# 03_Mechanicals.net
KiCad netlist of a schematic drawn in Altium Designer
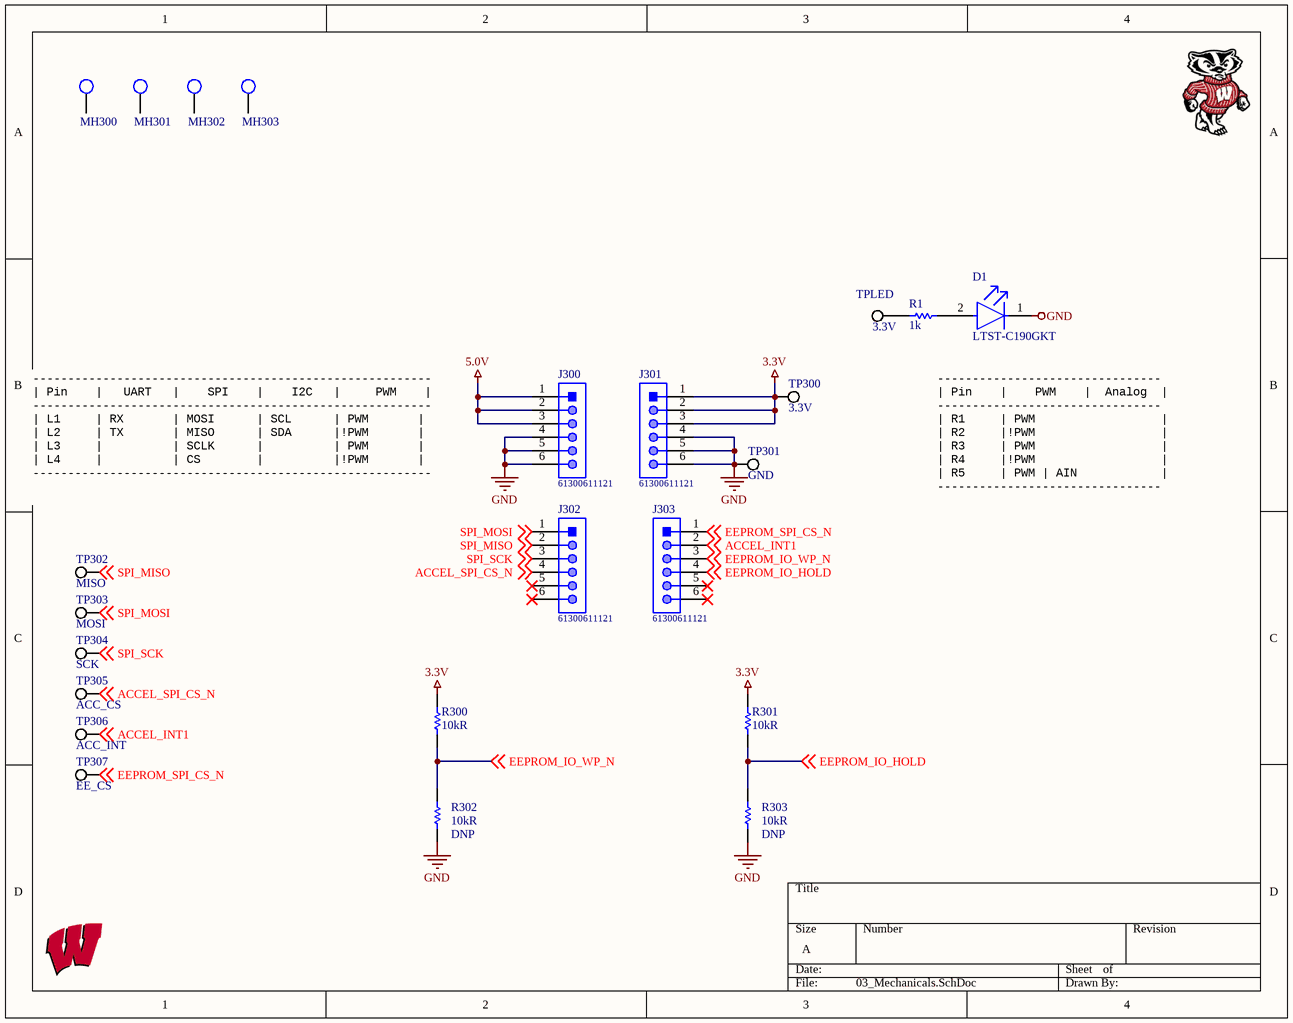
[diagram p0: 03_Mechanicals.SchDoc]

(export (version "E")
  (design (tool "Eeschema 10.0.6"))
  (components
    (comp (ref "D1")
      (value "LTST-C190GKT")
      (footprint "FP-LTST-C190GKT-MFG")
      (description "LED GREEN CLEAR CHIP SMD")
      (fields (field (name "VOLTAGE") "2V"))
      (libsource (lib "Altium Content Vault") (part "8706943c75ba83719d021d2fdc84c58"))
    )
    (comp (ref "J300")
      (value "61300611121")
      (footprint "61300611121")
      (description "THT Vertical Pin Header WR-PHD, Pitch 2.54 mm, Single Row, 6 pins")
      (fields (field (name "MANUFACTURER") "Wurth Elektronik") (field (name "PUBLISHER") "WurthElektronik"))
      (libsource (lib "") (part "WE-CN-1P-M-R6_1"))
    )
    (comp (ref "J301")
      (value "61300611121")
      (footprint "61300611121")
      (description "THT Vertical Pin Header WR-PHD, Pitch 2.54 mm, Single Row, 6 pins")
      (fields (field (name "MANUFACTURER") "Wurth Elektronik") (field (name "PUBLISHER") "WurthElektronik"))
      (libsource (lib "Altium Content Vault") (part "WE-CN-1P-M-R6"))
    )
    (comp (ref "J302")
      (value "61300611121")
      (footprint "61300611121")
      (description "THT Vertical Pin Header WR-PHD, Pitch 2.54 mm, Single Row, 6 pins")
      (fields (field (name "MANUFACTURER") "Wurth Elektronik") (field (name "PUBLISHER") "WurthElektronik"))
      (libsource (lib "") (part "WE-CN-1P-M-R6_1"))
    )
    (comp (ref "J303")
      (value "61300611121")
      (footprint "61300611121")
      (description "THT Vertical Pin Header WR-PHD, Pitch 2.54 mm, Single Row, 6 pins")
      (fields (field (name "MANUFACTURER") "Wurth Elektronik") (field (name "PUBLISHER") "WurthElektronik"))
      (libsource (lib "Altium Content Vault") (part "WE-CN-1P-M-R6"))
    )
    (comp (ref "MH300")
      (value "MHOLE_2_55MM")
      (footprint "MHOLE_2_55MM")
      (description "Mounting Holde")
      (fields (field (name "MANUFACTURER PART NUMBER") "UW MTHOLE"))
      (libsource (lib "ece315-2018-fall") (part "MHOLE_2_55MM"))
    )
    (comp (ref "MH301")
      (value "MHOLE_2_55MM")
      (footprint "MHOLE_2_55MM")
      (description "Mounting Holde")
      (fields (field (name "MANUFACTURER PART NUMBER") "UW MTHOLE"))
      (libsource (lib "ece315-2018-fall") (part "MHOLE_2_55MM"))
    )
    (comp (ref "MH302")
      (value "MHOLE_2_55MM")
      (footprint "MHOLE_2_55MM")
      (description "Mounting Holde")
      (fields (field (name "MANUFACTURER PART NUMBER") "UW MTHOLE"))
      (libsource (lib "ece315-2018-fall") (part "MHOLE_2_55MM"))
    )
    (comp (ref "MH303")
      (value "MHOLE_2_55MM")
      (footprint "MHOLE_2_55MM")
      (description "Mounting Holde")
      (fields (field (name "MANUFACTURER PART NUMBER") "UW MTHOLE"))
      (libsource (lib "ece315-2018-fall") (part "MHOLE_2_55MM"))
    )
    (comp (ref "R1")
      (value "1k")
      (footprint "RESC2013X60X35ML10T20")
      (description "Chip Resistor, 1 KOhm, +/- 1%, 125 mW, -55 to 155 degC, 0805 (2012 Metric), RoHS, Tape and Reel")
      (fields (field (name "TOLERANCE") "1%") (field (name "MANUFACTURER") "Yageo"))
      (libsource (lib "Altium Content Vault") (part "RES-2"))
    )
    (comp (ref "R300")
      (value "RC0805FR-0710KL")
      (footprint "RESC2013X60X35NL10T20")
      (description "Chip Resistor, 10 KOhm, +/- 1%, 0.125 W, -55 to 155 degC, 0805 (2012 Metric), RoHS, Tape and Reel")
      (fields
        (field (name "MANUFACTURER") "Yageo")
        (field (name "RESISTANCE") "10kR")
        (field (name "TOLERANCE") "1%")
      )
      (libsource (lib "Altium Content Vault") (part "RES-2"))
    )
    (comp (ref "R301")
      (value "RC0805FR-0710KL")
      (footprint "RESC2013X60X35NL10T20")
      (description "Chip Resistor, 10 KOhm, +/- 1%, 0.125 W, -55 to 155 degC, 0805 (2012 Metric), RoHS, Tape and Reel")
      (fields
        (field (name "MANUFACTURER") "Yageo")
        (field (name "RESISTANCE") "10kR")
        (field (name "TOLERANCE") "1%")
      )
      (libsource (lib "Altium Content Vault") (part "RES-2"))
    )
    (comp (ref "R302")
      (value "DNP")
      (footprint "RESC2013X60X35NL10T20")
      (description "Chip Resistor, 10 KOhm, +/- 1%, 0.125 W, -55 to 155 degC, 0805 (2012 Metric), RoHS, Tape and Reel")
      (fields
        (field (name "MANUFACTURER") "Yageo")
        (field (name "RESISTANCE") "10kR")
        (field (name "TOLERANCE") "1%")
      )
      (libsource (lib "Altium Content Vault") (part "RES-2"))
    )
    (comp (ref "R303")
      (value "DNP")
      (footprint "RESC2013X60X35NL10T20")
      (description "Chip Resistor, 10 KOhm, +/- 1%, 0.125 W, -55 to 155 degC, 0805 (2012 Metric), RoHS, Tape and Reel")
      (fields
        (field (name "MANUFACTURER") "Yageo")
        (field (name "RESISTANCE") "10kR")
        (field (name "TOLERANCE") "1%")
      )
      (libsource (lib "Altium Content Vault") (part "RES-2"))
    )
    (comp (ref "TP300")
      (value "3.3V")
      (footprint "KSTN-5019_V")
      (description "Test Point, 1 Position SMD, RoHS, Tape and Reel")
      (libsource (lib "Altium Content Vault") (part "TESTPOINT_WHITE"))
    )
    (comp (ref "TP301")
      (value "GND")
      (footprint "KSTN-5019_V")
      (description "Test Point, 1 Position SMD, RoHS, Tape and Reel")
      (libsource (lib "Altium Content Vault") (part "TESTPOINT_WHITE"))
    )
    (comp (ref "TP302")
      (value "MISO")
      (footprint "KSTN-5019_V")
      (description "Test Point, 1 Position SMD, RoHS, Tape and Reel")
      (libsource (lib "Altium Content Vault") (part "TESTPOINT_WHITE"))
    )
    (comp (ref "TP303")
      (value "MOSI")
      (footprint "KSTN-5019_V")
      (description "Test Point, 1 Position SMD, RoHS, Tape and Reel")
      (libsource (lib "Altium Content Vault") (part "TESTPOINT_WHITE"))
    )
    (comp (ref "TP304")
      (value "SCK")
      (footprint "KSTN-5019_V")
      (description "Test Point, 1 Position SMD, RoHS, Tape and Reel")
      (libsource (lib "Altium Content Vault") (part "TESTPOINT_WHITE"))
    )
    (comp (ref "TP305")
      (value "ACC_CS")
      (footprint "KSTN-5019_V")
      (description "Test Point, 1 Position SMD, RoHS, Tape and Reel")
      (libsource (lib "Altium Content Vault") (part "TESTPOINT_WHITE"))
    )
    (comp (ref "TP306")
      (value "ACC_INT")
      (footprint "KSTN-5019_V")
      (description "Test Point, 1 Position SMD, RoHS, Tape and Reel")
      (libsource (lib "Altium Content Vault") (part "TESTPOINT_WHITE"))
    )
    (comp (ref "TP307")
      (value "EE_CS")
      (footprint "KSTN-5019_V")
      (description "Test Point, 1 Position SMD, RoHS, Tape and Reel")
      (libsource (lib "Altium Content Vault") (part "TESTPOINT_WHITE"))
    )
    (comp (ref "TPLED")
      (value "3.3V")
      (footprint "KSTN-5019_V")
      (description "Test Point, 1 Position SMD, RoHS, Tape and Reel")
      (libsource (lib "Altium Content Vault") (part "TESTPOINT_WHITE"))
    )
  )
  (nets
    (net (code "1") (name "3.3V") (class "Default")
      (node (ref "J301") (pin "1") (pinfunction "1_1") (pintype "passive"))
      (node (ref "J301") (pin "2") (pinfunction "2_2") (pintype "passive"))
      (node (ref "J301") (pin "3") (pinfunction "3_3") (pintype "passive"))
      (node (ref "R300") (pin "1") (pinfunction "1_1") (pintype "passive"))
      (node (ref "R301") (pin "1") (pinfunction "1_1") (pintype "passive"))
      (node (ref "TP300") (pin "1") (pinfunction "1_1") (pintype "passive"))
    )
    (net (code "2") (name "5.0V") (class "Default")
      (node (ref "J300") (pin "1") (pinfunction "1_1") (pintype "passive"))
      (node (ref "J300") (pin "2") (pinfunction "2_2") (pintype "passive"))
      (node (ref "J300") (pin "3") (pinfunction "3_3") (pintype "passive"))
    )
    (net (code "3") (name "ACCEL_INT1") (class "Default")
      (node (ref "J303") (pin "2") (pinfunction "2_2") (pintype "passive"))
      (node (ref "TP306") (pin "1") (pinfunction "1_1") (pintype "passive"))
    )
    (net (code "4") (name "ACCEL_SPI_CS_N") (class "Default")
      (node (ref "J302") (pin "4") (pinfunction "4_4") (pintype "passive"))
      (node (ref "TP305") (pin "1") (pinfunction "1_1") (pintype "passive"))
    )
    (net (code "5") (name "EEPROM_IO_HOLD") (class "Default")
      (node (ref "J303") (pin "4") (pinfunction "4_4") (pintype "passive"))
      (node (ref "R301") (pin "2") (pinfunction "2_2") (pintype "passive"))
      (node (ref "R303") (pin "1") (pinfunction "1_1") (pintype "passive"))
    )
    (net (code "6") (name "EEPROM_IO_WP_N") (class "Default")
      (node (ref "J303") (pin "3") (pinfunction "3_3") (pintype "passive"))
      (node (ref "R300") (pin "2") (pinfunction "2_2") (pintype "passive"))
      (node (ref "R302") (pin "1") (pinfunction "1_1") (pintype "passive"))
    )
    (net (code "7") (name "EEPROM_SPI_CS_N") (class "Default")
      (node (ref "J303") (pin "1") (pinfunction "1_1") (pintype "passive"))
      (node (ref "TP307") (pin "1") (pinfunction "1_1") (pintype "passive"))
    )
    (net (code "8") (name "GND") (class "Default")
      (node (ref "D1") (pin "1") (pinfunction "C_1") (pintype "passive"))
      (node (ref "J300") (pin "4") (pinfunction "4_4") (pintype "passive"))
      (node (ref "J300") (pin "5") (pinfunction "5_5") (pintype "passive"))
      (node (ref "J300") (pin "6") (pinfunction "6_6") (pintype "passive"))
      (node (ref "J301") (pin "4") (pinfunction "4_4") (pintype "passive"))
      (node (ref "J301") (pin "5") (pinfunction "5_5") (pintype "passive"))
      (node (ref "J301") (pin "6") (pinfunction "6_6") (pintype "passive"))
      (node (ref "R302") (pin "2") (pinfunction "2_2") (pintype "passive"))
      (node (ref "R303") (pin "2") (pinfunction "2_2") (pintype "passive"))
      (node (ref "TP301") (pin "1") (pinfunction "1_1") (pintype "passive"))
    )
    (net (code "9") (name "Net-(D1-A)") (class "Default")
      (node (ref "D1") (pin "2") (pinfunction "A_2") (pintype "passive"))
      (node (ref "R1") (pin "1") (pinfunction "1_1") (pintype "passive"))
    )
    (net (code "10") (name "Net-(R1-Pad2)") (class "Default")
      (node (ref "R1") (pin "2") (pinfunction "2_2") (pintype "passive"))
      (node (ref "TPLED") (pin "1") (pinfunction "1_1") (pintype "passive"))
    )
    (net (code "11") (name "SPI_MISO") (class "Default")
      (node (ref "J302") (pin "2") (pinfunction "2_2") (pintype "passive"))
      (node (ref "TP302") (pin "1") (pinfunction "1_1") (pintype "passive"))
    )
    (net (code "12") (name "SPI_MOSI") (class "Default")
      (node (ref "J302") (pin "1") (pinfunction "1_1") (pintype "passive"))
      (node (ref "TP303") (pin "1") (pinfunction "1_1") (pintype "passive"))
    )
    (net (code "13") (name "SPI_SCK") (class "Default")
      (node (ref "J302") (pin "3") (pinfunction "3_3") (pintype "passive"))
      (node (ref "TP304") (pin "1") (pinfunction "1_1") (pintype "passive"))
    )
    (net (code "14") (name "unconnected-(J302-Pad5)") (class "Default")
      (node (ref "J302") (pin "5") (pinfunction "5_5") (pintype "passive+no_connect"))
    )
    (net (code "15") (name "unconnected-(J302-Pad6)") (class "Default")
      (node (ref "J302") (pin "6") (pinfunction "6_6") (pintype "passive+no_connect"))
    )
    (net (code "16") (name "unconnected-(J303-Pad5)") (class "Default")
      (node (ref "J303") (pin "5") (pinfunction "5_5") (pintype "passive+no_connect"))
    )
    (net (code "17") (name "unconnected-(J303-Pad6)") (class "Default")
      (node (ref "J303") (pin "6") (pinfunction "6_6") (pintype "passive+no_connect"))
    )
    (net (code "18") (name "unconnected-(MH300-Pad1)") (class "Default")
      (node (ref "MH300") (pin "1") (pintype "passive"))
    )
    (net (code "19") (name "unconnected-(MH301-Pad1)") (class "Default")
      (node (ref "MH301") (pin "1") (pintype "passive"))
    )
    (net (code "20") (name "unconnected-(MH302-Pad1)") (class "Default")
      (node (ref "MH302") (pin "1") (pintype "passive"))
    )
    (net (code "21") (name "unconnected-(MH303-Pad1)") (class "Default")
      (node (ref "MH303") (pin "1") (pintype "passive"))
    )
  )
)
